# EQ_B.net
KiCad netlist of a schematic drawn in Altium Designer
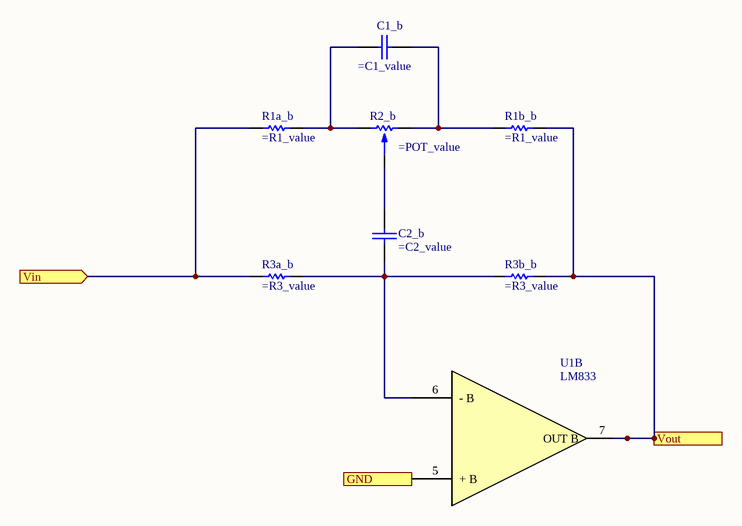
[diagram p0: EQ_B.SchDoc]

(export (version "E")
  (design (tool "Eeschema 10.0.6"))
  (components
    (comp (ref "C1_b") (value "~") (footprint "CAP200") (libsource (lib "LIBEBAL") (part "CAP")))
    (comp (ref "C2_b") (value "~") (footprint "CAP200") (libsource (lib "LIBEBAL") (part "CAP")))
    (comp (ref "R1a_b") (value "~") (footprint "0805") (libsource (lib "LIBEBAL") (part "RES")))
    (comp (ref "R1b_b") (value "~") (footprint "0805") (libsource (lib "LIBEBAL") (part "RES")))
    (comp (ref "R2_b")
      (value "~")
      (footprint "POTENCIOMETRO")
      (libsource (lib "LIBEBAL") (part "POTENCIOMETRO"))
    )
    (comp (ref "R3a_b") (value "~") (footprint "0805") (libsource (lib "LIBEBAL") (part "RES")))
    (comp (ref "R3b_b") (value "~") (footprint "0805") (libsource (lib "LIBEBAL") (part "RES")))
    (comp (ref "U1")
      (value "LM833")
      (footprint "DIP8")
      (description "Dual Audio Operational Amplifier")
      (libsource (lib "LIBEBAL") (part "LM833"))
    )
  )
  (nets
    (net (code "1") (name "/GND") (class "Default")
      (node (ref "U1") (pin "5") (pinfunction "+_B_5") (pintype "passive"))
    )
    (net (code "2") (name "/Vin") (class "Default")
      (node (ref "R1a_b") (pin "1") (pinfunction "1_1") (pintype "passive"))
      (node (ref "R3a_b") (pin "1") (pinfunction "1_1") (pintype "passive"))
    )
    (net (code "3") (name "/Vout") (class "Default")
      (node (ref "R1b_b") (pin "2") (pinfunction "2_2") (pintype "passive"))
      (node (ref "R3b_b") (pin "2") (pinfunction "2_2") (pintype "passive"))
      (node (ref "U1") (pin "7") (pinfunction "OUT_B_7") (pintype "passive"))
    )
    (net (code "4") (name "Net-(C1_b-Pad1)") (class "Default")
      (node (ref "C1_b") (pin "1") (pinfunction "1_1") (pintype "passive"))
      (node (ref "R1a_b") (pin "2") (pinfunction "2_2") (pintype "passive"))
      (node (ref "R2_b") (pin "3") (pinfunction "3_3") (pintype "passive"))
    )
    (net (code "5") (name "Net-(C1_b-Pad2)") (class "Default")
      (node (ref "C1_b") (pin "2") (pinfunction "2_2") (pintype "passive"))
      (node (ref "R1b_b") (pin "1") (pinfunction "1_1") (pintype "passive"))
      (node (ref "R2_b") (pin "1") (pinfunction "1_1") (pintype "passive"))
    )
    (net (code "6") (name "Net-(C2_b-Pad1)") (class "Default")
      (node (ref "C2_b") (pin "1") (pinfunction "1_1") (pintype "passive"))
      (node (ref "R2_b") (pin "2") (pinfunction "2_2") (pintype "passive"))
    )
    (net (code "7") (name "Net-(U1B--_B)") (class "Default")
      (node (ref "C2_b") (pin "2") (pinfunction "2_2") (pintype "passive"))
      (node (ref "R3a_b") (pin "2") (pinfunction "2_2") (pintype "passive"))
      (node (ref "R3b_b") (pin "1") (pinfunction "1_1") (pintype "passive"))
      (node (ref "U1") (pin "6") (pinfunction "-_B_6") (pintype "passive"))
    )
  )
)
